# LeoPager.net
KiCad netlist of a schematic drawn in EAGLE
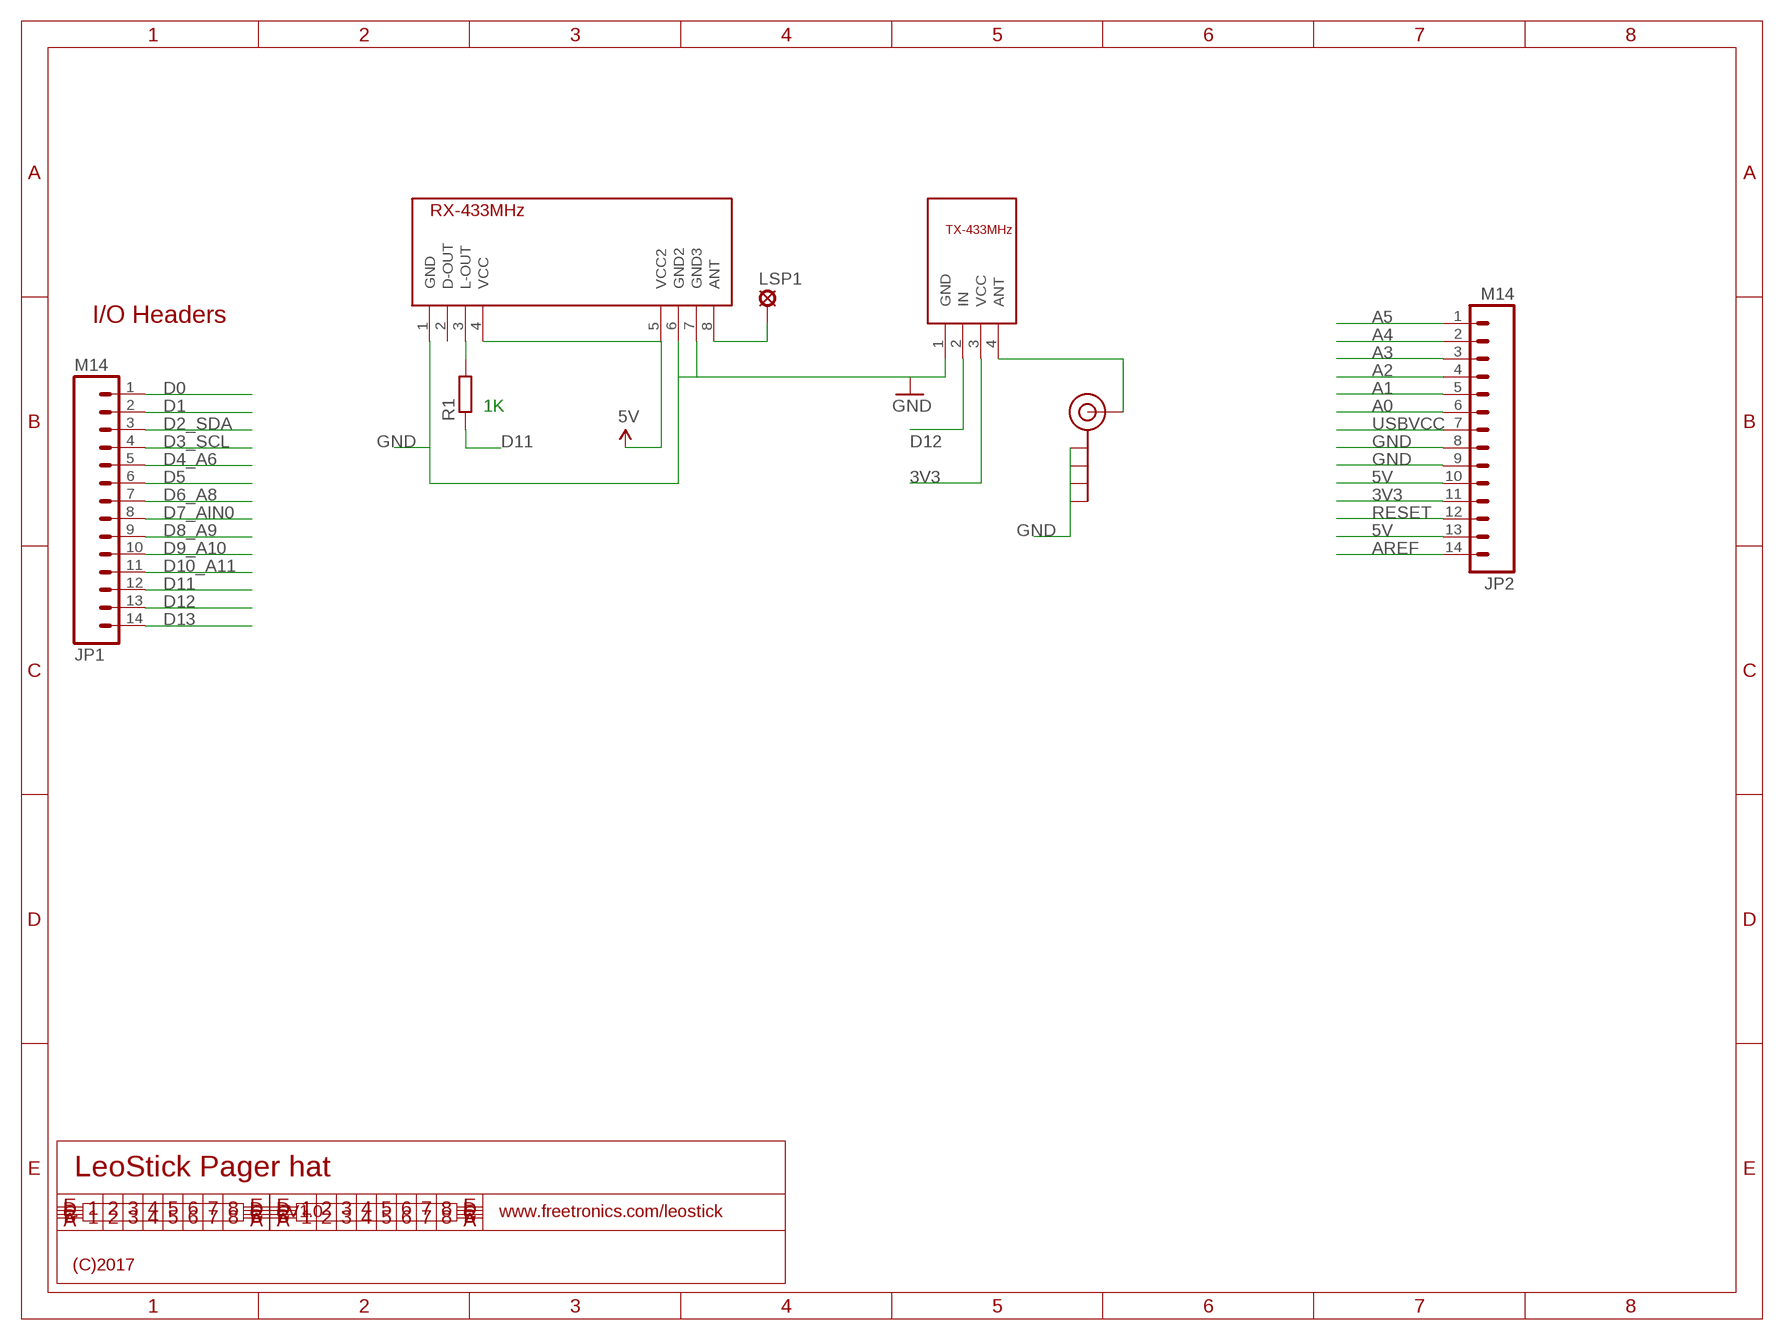
[diagram p0: schematic, sheet 1]

(export (version "E")
  (design (tool "Eeschema 10.0.6"))
  (components
    (comp (ref "J$1")
      (value "SMA_EDGE")
      (footprint "eagle-import:SMA-EDGE")
      (libsource (lib "eagle-import") (part "SMA_EDGE"))
    )
    (comp (ref "JP1")
      (value "M14")
      (footprint "eagle-import:1X14")
      (libsource (lib "eagle-import") (part "M14"))
    )
    (comp (ref "JP2")
      (value "M14")
      (footprint "eagle-import:1X14")
      (libsource (lib "eagle-import") (part "M14"))
    )
    (comp (ref "LSP1")
      (value "LSP10")
      (footprint "eagle-import:LSP10")
      (libsource (lib "eagle-import") (part "LSP10"))
    )
    (comp (ref "R1")
      (value "R-EU_0204/7")
      (footprint "eagle-import:0204_7")
      (libsource (lib "eagle-import") (part "R-EU_0204/7"))
    )
    (comp (ref "RF-MODULE1")
      (value "RX-433MHZ")
      (footprint "eagle-import:RX-433MHZ")
      (libsource (lib "eagle-import") (part "RX-433MHZ"))
    )
    (comp (ref "RF-MODULE2")
      (value "TX-433MHZ")
      (footprint "eagle-import:TX-433MHZ")
      (libsource (lib "eagle-import") (part "TX-433MHZ"))
    )
  )
  (nets
    (net (code "1") (name "/3V3") (class "Default")
      (node (ref "JP2") (pin "11") (pinfunction "11_11") (pintype "passive"))
      (node (ref "RF-MODULE2") (pin "3") (pinfunction "VCC_3") (pintype "power_in"))
    )
    (net (code "2") (name "/A0") (class "Default")
      (node (ref "JP2") (pin "6") (pinfunction "6_6") (pintype "passive"))
    )
    (net (code "3") (name "/A1") (class "Default")
      (node (ref "JP2") (pin "5") (pinfunction "5_5") (pintype "passive"))
    )
    (net (code "4") (name "/A2") (class "Default")
      (node (ref "JP2") (pin "4") (pinfunction "4_4") (pintype "passive"))
    )
    (net (code "5") (name "/A3") (class "Default")
      (node (ref "JP2") (pin "3") (pinfunction "3_3") (pintype "passive"))
    )
    (net (code "6") (name "/A4") (class "Default")
      (node (ref "JP2") (pin "2") (pinfunction "2_2") (pintype "passive"))
    )
    (net (code "7") (name "/A5") (class "Default")
      (node (ref "JP2") (pin "1") (pinfunction "1_1") (pintype "passive"))
    )
    (net (code "8") (name "/AREF") (class "Default")
      (node (ref "JP2") (pin "14") (pinfunction "14_14") (pintype "passive"))
    )
    (net (code "9") (name "/D0") (class "Default")
      (node (ref "JP1") (pin "1") (pinfunction "1_1") (pintype "passive"))
    )
    (net (code "10") (name "/D1") (class "Default")
      (node (ref "JP1") (pin "2") (pinfunction "2_2") (pintype "passive"))
    )
    (net (code "11") (name "/D2_SDA") (class "Default")
      (node (ref "JP1") (pin "3") (pinfunction "3_3") (pintype "passive"))
    )
    (net (code "12") (name "/D3_SCL") (class "Default")
      (node (ref "JP1") (pin "4") (pinfunction "4_4") (pintype "passive"))
    )
    (net (code "13") (name "/D4_A6") (class "Default")
      (node (ref "JP1") (pin "5") (pinfunction "5_5") (pintype "passive"))
    )
    (net (code "14") (name "/D5") (class "Default")
      (node (ref "JP1") (pin "6") (pinfunction "6_6") (pintype "passive"))
    )
    (net (code "15") (name "/D6_A8") (class "Default")
      (node (ref "JP1") (pin "7") (pinfunction "7_7") (pintype "passive"))
    )
    (net (code "16") (name "/D7_AIN0") (class "Default")
      (node (ref "JP1") (pin "8") (pinfunction "8_8") (pintype "passive"))
    )
    (net (code "17") (name "/D8_A9") (class "Default")
      (node (ref "JP1") (pin "9") (pinfunction "9_9") (pintype "passive"))
    )
    (net (code "18") (name "/D9_A10") (class "Default")
      (node (ref "JP1") (pin "10") (pinfunction "10_10") (pintype "passive"))
    )
    (net (code "19") (name "/D10_A11") (class "Default")
      (node (ref "JP1") (pin "11") (pinfunction "11_11") (pintype "passive"))
    )
    (net (code "20") (name "/D11") (class "Default")
      (node (ref "JP1") (pin "12") (pinfunction "12_12") (pintype "passive"))
      (node (ref "R1") (pin "1") (pinfunction "1_1") (pintype "passive"))
    )
    (net (code "21") (name "/D12") (class "Default")
      (node (ref "JP1") (pin "13") (pinfunction "13_13") (pintype "passive"))
      (node (ref "RF-MODULE2") (pin "2") (pinfunction "IN_2") (pintype "input"))
    )
    (net (code "22") (name "/D13") (class "Default")
      (node (ref "JP1") (pin "14") (pinfunction "14_14") (pintype "passive"))
    )
    (net (code "23") (name "/RESET") (class "Default")
      (node (ref "JP2") (pin "12") (pinfunction "12_12") (pintype "passive"))
    )
    (net (code "24") (name "/USBVCC") (class "Default")
      (node (ref "JP2") (pin "7") (pinfunction "7_7") (pintype "passive"))
    )
    (net (code "25") (name "5V") (class "Default")
      (node (ref "JP2") (pin "10") (pinfunction "10_10") (pintype "passive"))
      (node (ref "JP2") (pin "13") (pinfunction "13_13") (pintype "passive"))
      (node (ref "RF-MODULE1") (pin "4") (pinfunction "VCC_4") (pintype "power_in"))
      (node (ref "RF-MODULE1") (pin "5") (pinfunction "VCC2_5") (pintype "power_in"))
    )
    (net (code "26") (name "GND") (class "Default")
      (node (ref "J$1") (pin "GND@0") (pinfunction "GND_GND@0") (pintype "bidirectional"))
      (node (ref "J$1") (pin "GND@1") (pinfunction "GND_GND@1") (pintype "bidirectional"))
      (node (ref "J$1") (pin "GND@2") (pinfunction "GND_GND@2") (pintype "bidirectional"))
      (node (ref "J$1") (pin "GND@3") (pinfunction "GND_GND@3") (pintype "bidirectional"))
      (node (ref "JP2") (pin "8") (pinfunction "8_8") (pintype "passive"))
      (node (ref "JP2") (pin "9") (pinfunction "9_9") (pintype "passive"))
      (node (ref "RF-MODULE1") (pin "1") (pinfunction "GND_1") (pintype "power_in"))
      (node (ref "RF-MODULE1") (pin "6") (pinfunction "GND2_6") (pintype "power_in"))
      (node (ref "RF-MODULE1") (pin "7") (pinfunction "GND3_7") (pintype "power_in"))
      (node (ref "RF-MODULE2") (pin "1") (pinfunction "GND_1") (pintype "power_in"))
    )
    (net (code "27") (name "Net-(J$1-SIGNAL)") (class "Default")
      (node (ref "J$1") (pin "SIG") (pinfunction "SIGNAL_SIG") (pintype "bidirectional"))
      (node (ref "RF-MODULE2") (pin "4") (pinfunction "ANT_4") (pintype "passive"))
    )
    (net (code "28") (name "Net-(RF-MODULE1-ANT)") (class "Default")
      (node (ref "LSP1") (pin "MP") (pinfunction "MP_MP") (pintype "passive"))
      (node (ref "RF-MODULE1") (pin "8") (pinfunction "ANT_8") (pintype "passive"))
    )
    (net (code "29") (name "Net-(RF-MODULE1-L-OUT)") (class "Default")
      (node (ref "R1") (pin "2") (pinfunction "2_2") (pintype "passive"))
      (node (ref "RF-MODULE1") (pin "3") (pinfunction "L-OUT_3") (pintype "output"))
    )
    (net (code "30") (name "unconnected-(RF-MODULE1-D-OUT-Pad2)") (class "Default")
      (node (ref "RF-MODULE1") (pin "2") (pinfunction "D-OUT_2") (pintype "output"))
    )
  )
)
